# CONNECTOR.net
KiCad netlist of a schematic drawn in Altium Designer
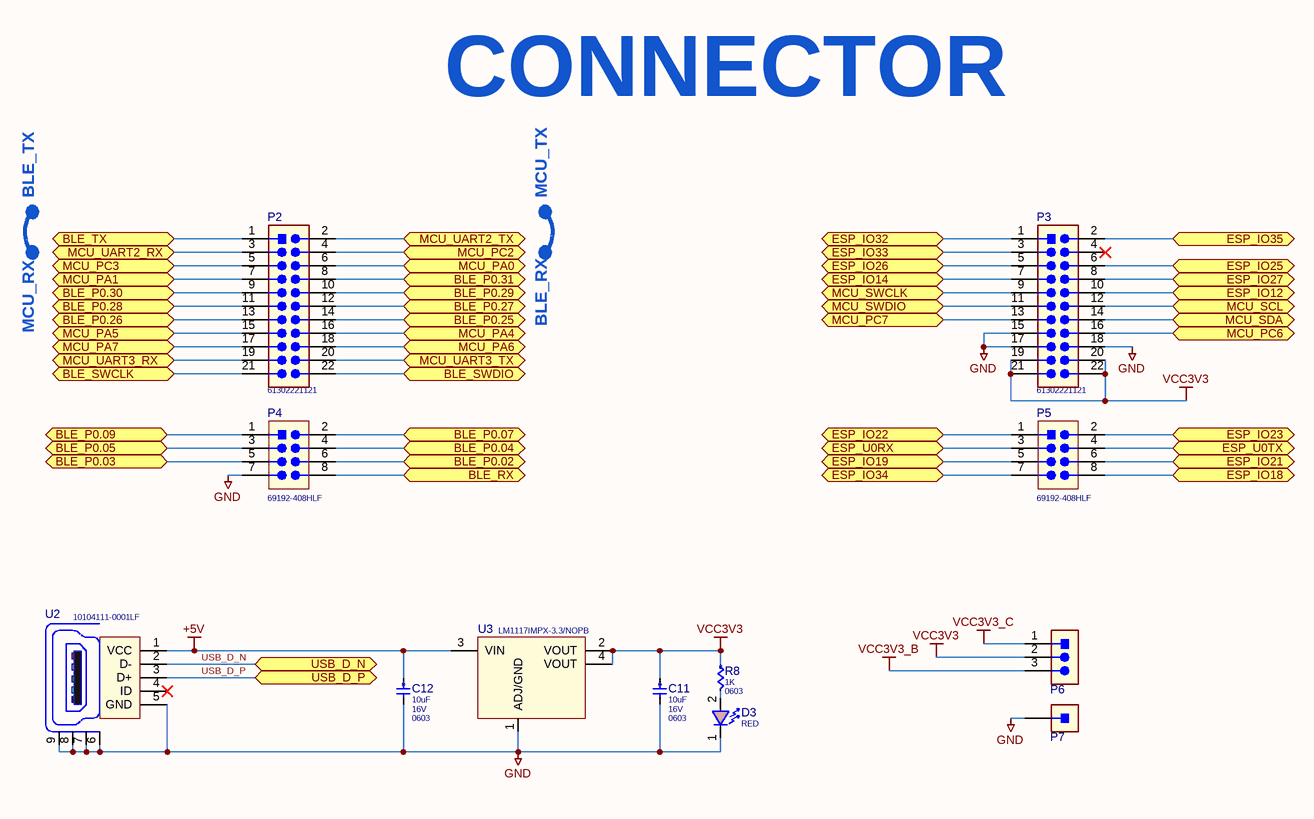
[diagram p0: CONNECTOR.SchDoc]

(export (version "E")
  (design (tool "Eeschema 10.0.6"))
  (components
    (comp (ref "C11")
      (value "10uF")
      (footprint "C0603")
      (description "CAP CER 10UF 10% 16V X5R 0603 SMD")
      (fields
        (field (name "TOLERANCE") "10%")
        (field (name "VOLTAGE") "16V")
        (field (name "PACK") "0603")
        (field (name "Comment") "10uF 16V 0603")
      )
      (libsource (lib "FENIKAA_LIB") (part "C0603_10uF_16V_10%"))
    )
    (comp (ref "C12")
      (value "10uF")
      (footprint "C0603")
      (description "CAP CER 10UF 10% 16V X5R 0603 SMD")
      (fields
        (field (name "TOLERANCE") "10%")
        (field (name "VOLTAGE") "16V")
        (field (name "PACK") "0603")
        (field (name "Comment") "10uF 16V 0603")
      )
      (libsource (lib "FENIKAA_LIB") (part "C0603_10uF_16V_10%"))
    )
    (comp (ref "D3")
      (value "LH R974-LP-1")
      (footprint "LED0805_RED")
      (description "LED IND RED 1.8V 20mA 0805 SMD")
      (fields (field (name "COLOR") "RED"))
      (libsource (lib "FENIKAA_LIB") (part "LED0805_RED"))
    )
    (comp (ref "P2")
      (value "61302221121")
      (footprint "CON_22_2.54")
      (description "CON C2B 2R11C M 2.54P THR")
      (fields (field (name "MGR PN") "61302221121"))
      (libsource (lib "FENIKAA_LIB") (part "CON_2x11"))
    )
    (comp (ref "P3")
      (value "61302221121")
      (footprint "CON_22_2.54")
      (description "CON C2B 2R11C M 2.54P THR")
      (fields (field (name "MGR PN") "61302221121"))
      (libsource (lib "FENIKAA_LIB") (part "CON_2x11"))
    )
    (comp (ref "P4")
      (value "69192-408HLF")
      (footprint "CON_2x4_2.54P")
      (description "CON C2B 2R4C M 2.54P THR")
      (fields (field (name "MGR PN") "69192-408HLF"))
      (libsource (lib "FENIKAA_LIB") (part "CON_2x4"))
    )
    (comp (ref "P5")
      (value "69192-408HLF")
      (footprint "CON_2x4_2.54P")
      (description "CON C2B 2R4C M 2.54P THR")
      (fields (field (name "MGR PN") "69192-408HLF"))
      (libsource (lib "FENIKAA_LIB") (part "CON_2x4"))
    )
    (comp (ref "P6")
      (value "CON3")
      (footprint "CON_3_2.54")
      (description "CONNECTOR 3POS 2.54")
      (libsource (lib "FENIKAA_LIB") (part "CON3"))
    )
    (comp (ref "P7")
      (value "PAD_2.54")
      (footprint "CONN_1")
      (libsource (lib "FENIKAA_LIB") (part "PAD_2.54"))
    )
    (comp (ref "R8")
      (value "1K")
      (footprint "R0603")
      (description "RES CHP 1K 1% 1/10W 0603 SMD")
      (fields (field (name "POWER") "1/10W") (field (name "PACK") "0603") (field (name "TOLERANCE") "1%"))
      (libsource (lib "FENIKAA_LIB") (part "R0603_1K_1/10W_1%"))
    )
    (comp (ref "U2")
      (value "10104111-0001LF")
      (footprint "USB-MICRO-AB")
      (description "CON USB 2.0 MICRO AB SMD")
      (fields (field (name "MGR PN") "10104111-0001LF"))
      (libsource (lib "FENIKAA_LIB") (part "CON_USB_MICRO"))
    )
    (comp (ref "U3")
      (value "LM1117IMPX-3.3/NOPB")
      (footprint "SOT-223-4")
      (description "ICS PMI VREG 3.3V 800mA SOT-223-4 SMD")
      (fields (field (name "MGR PN") "LM1117IMPX-3.3/NOPB"))
      (libsource (lib "FENIKAA_LIB") (part "IC_LM1117IMPX-3.3/NOPB"))
    )
  )
  (nets
    (net (code "1") (name "+5V") (class "Default")
      (node (ref "C12") (pin "1") (pinfunction "1_1") (pintype "passive"))
      (node (ref "U2") (pin "1") (pinfunction "VCC_1") (pintype "passive"))
      (node (ref "U3") (pin "3") (pinfunction "VIN_3") (pintype "passive"))
    )
    (net (code "2") (name "/BLE_P0.02") (class "Default")
      (node (ref "P4") (pin "6") (pinfunction "6_6") (pintype "passive"))
    )
    (net (code "3") (name "/BLE_P0.03") (class "Default")
      (node (ref "P4") (pin "5") (pinfunction "5_5") (pintype "passive"))
    )
    (net (code "4") (name "/BLE_P0.04") (class "Default")
      (node (ref "P4") (pin "4") (pinfunction "4_4") (pintype "passive"))
    )
    (net (code "5") (name "/BLE_P0.05") (class "Default")
      (node (ref "P4") (pin "3") (pinfunction "3_3") (pintype "passive"))
    )
    (net (code "6") (name "/BLE_P0.07") (class "Default")
      (node (ref "P4") (pin "2") (pinfunction "2_2") (pintype "passive"))
    )
    (net (code "7") (name "/BLE_P0.09") (class "Default")
      (node (ref "P4") (pin "1") (pinfunction "1_1") (pintype "passive"))
    )
    (net (code "8") (name "/BLE_P0.25") (class "Default")
      (node (ref "P2") (pin "14") (pinfunction "14_14") (pintype "passive"))
    )
    (net (code "9") (name "/BLE_P0.26") (class "Default")
      (node (ref "P2") (pin "13") (pinfunction "13_13") (pintype "passive"))
    )
    (net (code "10") (name "/BLE_P0.27") (class "Default")
      (node (ref "P2") (pin "12") (pinfunction "12_12") (pintype "passive"))
    )
    (net (code "11") (name "/BLE_P0.28") (class "Default")
      (node (ref "P2") (pin "11") (pinfunction "11_11") (pintype "passive"))
    )
    (net (code "12") (name "/BLE_P0.29") (class "Default")
      (node (ref "P2") (pin "10") (pinfunction "10_10") (pintype "passive"))
    )
    (net (code "13") (name "/BLE_P0.30") (class "Default")
      (node (ref "P2") (pin "9") (pinfunction "9_9") (pintype "passive"))
    )
    (net (code "14") (name "/BLE_P0.31") (class "Default")
      (node (ref "P2") (pin "8") (pinfunction "8_8") (pintype "passive"))
    )
    (net (code "15") (name "/BLE_RX") (class "Default")
      (node (ref "P4") (pin "8") (pinfunction "8_8") (pintype "passive"))
    )
    (net (code "16") (name "/BLE_SWCLK") (class "Default")
      (node (ref "P2") (pin "21") (pinfunction "21_21") (pintype "passive"))
    )
    (net (code "17") (name "/BLE_SWDIO") (class "Default")
      (node (ref "P2") (pin "22") (pinfunction "22_22") (pintype "passive"))
    )
    (net (code "18") (name "/BLE_TX") (class "Default")
      (node (ref "P2") (pin "1") (pinfunction "1_1") (pintype "passive"))
    )
    (net (code "19") (name "/ESP_IO12") (class "Default")
      (node (ref "P3") (pin "10") (pinfunction "10_10") (pintype "passive"))
    )
    (net (code "20") (name "/ESP_IO14") (class "Default")
      (node (ref "P3") (pin "7") (pinfunction "7_7") (pintype "passive"))
    )
    (net (code "21") (name "/ESP_IO18") (class "Default")
      (node (ref "P5") (pin "8") (pinfunction "8_8") (pintype "passive"))
    )
    (net (code "22") (name "/ESP_IO19") (class "Default")
      (node (ref "P5") (pin "5") (pinfunction "5_5") (pintype "passive"))
    )
    (net (code "23") (name "/ESP_IO21") (class "Default")
      (node (ref "P5") (pin "6") (pinfunction "6_6") (pintype "passive"))
    )
    (net (code "24") (name "/ESP_IO22") (class "Default")
      (node (ref "P5") (pin "1") (pinfunction "1_1") (pintype "passive"))
    )
    (net (code "25") (name "/ESP_IO23") (class "Default")
      (node (ref "P5") (pin "2") (pinfunction "2_2") (pintype "passive"))
    )
    (net (code "26") (name "/ESP_IO25") (class "Default")
      (node (ref "P3") (pin "6") (pinfunction "6_6") (pintype "passive"))
    )
    (net (code "27") (name "/ESP_IO26") (class "Default")
      (node (ref "P3") (pin "5") (pinfunction "5_5") (pintype "passive"))
    )
    (net (code "28") (name "/ESP_IO27") (class "Default")
      (node (ref "P3") (pin "8") (pinfunction "8_8") (pintype "passive"))
    )
    (net (code "29") (name "/ESP_IO32") (class "Default")
      (node (ref "P3") (pin "1") (pinfunction "1_1") (pintype "passive"))
    )
    (net (code "30") (name "/ESP_IO33") (class "Default")
      (node (ref "P3") (pin "3") (pinfunction "3_3") (pintype "passive"))
    )
    (net (code "31") (name "/ESP_IO34") (class "Default")
      (node (ref "P5") (pin "7") (pinfunction "7_7") (pintype "passive"))
    )
    (net (code "32") (name "/ESP_IO35") (class "Default")
      (node (ref "P3") (pin "2") (pinfunction "2_2") (pintype "passive"))
    )
    (net (code "33") (name "/ESP_U0RX") (class "Default")
      (node (ref "P5") (pin "3") (pinfunction "3_3") (pintype "passive"))
    )
    (net (code "34") (name "/ESP_U0TX") (class "Default")
      (node (ref "P5") (pin "4") (pinfunction "4_4") (pintype "passive"))
    )
    (net (code "35") (name "/MCU_PA0") (class "Default")
      (node (ref "P2") (pin "6") (pinfunction "6_6") (pintype "passive"))
    )
    (net (code "36") (name "/MCU_PA1") (class "Default")
      (node (ref "P2") (pin "7") (pinfunction "7_7") (pintype "passive"))
    )
    (net (code "37") (name "/MCU_PA4") (class "Default")
      (node (ref "P2") (pin "16") (pinfunction "16_16") (pintype "passive"))
    )
    (net (code "38") (name "/MCU_PA5") (class "Default")
      (node (ref "P2") (pin "15") (pinfunction "15_15") (pintype "passive"))
    )
    (net (code "39") (name "/MCU_PA6") (class "Default")
      (node (ref "P2") (pin "18") (pinfunction "18_18") (pintype "passive"))
    )
    (net (code "40") (name "/MCU_PA7") (class "Default")
      (node (ref "P2") (pin "17") (pinfunction "17_17") (pintype "passive"))
    )
    (net (code "41") (name "/MCU_PC2") (class "Default")
      (node (ref "P2") (pin "4") (pinfunction "4_4") (pintype "passive"))
    )
    (net (code "42") (name "/MCU_PC3") (class "Default")
      (node (ref "P2") (pin "5") (pinfunction "5_5") (pintype "passive"))
    )
    (net (code "43") (name "/MCU_PC6") (class "Default")
      (node (ref "P3") (pin "16") (pinfunction "16_16") (pintype "passive"))
    )
    (net (code "44") (name "/MCU_PC7") (class "Default")
      (node (ref "P3") (pin "13") (pinfunction "13_13") (pintype "passive"))
    )
    (net (code "45") (name "/MCU_SCL") (class "Default")
      (node (ref "P3") (pin "12") (pinfunction "12_12") (pintype "passive"))
    )
    (net (code "46") (name "/MCU_SDA") (class "Default")
      (node (ref "P3") (pin "14") (pinfunction "14_14") (pintype "passive"))
    )
    (net (code "47") (name "/MCU_SWCLK") (class "Default")
      (node (ref "P3") (pin "9") (pinfunction "9_9") (pintype "passive"))
    )
    (net (code "48") (name "/MCU_SWDIO") (class "Default")
      (node (ref "P3") (pin "11") (pinfunction "11_11") (pintype "passive"))
    )
    (net (code "49") (name "/MCU_UART2_RX") (class "Default")
      (node (ref "P2") (pin "3") (pinfunction "3_3") (pintype "passive"))
    )
    (net (code "50") (name "/MCU_UART2_TX") (class "Default")
      (node (ref "P2") (pin "2") (pinfunction "2_2") (pintype "passive"))
    )
    (net (code "51") (name "/MCU_UART3_RX") (class "Default")
      (node (ref "P2") (pin "19") (pinfunction "19_19") (pintype "passive"))
    )
    (net (code "52") (name "/MCU_UART3_TX") (class "Default")
      (node (ref "P2") (pin "20") (pinfunction "20_20") (pintype "passive"))
    )
    (net (code "53") (name "/USB_D_N") (class "Default")
      (node (ref "U2") (pin "2") (pinfunction "D-_2") (pintype "passive"))
    )
    (net (code "54") (name "/USB_D_P") (class "Default")
      (node (ref "U2") (pin "3") (pinfunction "D+_3") (pintype "passive"))
    )
    (net (code "55") (name "GND") (class "Default")
      (node (ref "C11") (pin "2") (pinfunction "2_2") (pintype "passive"))
      (node (ref "C12") (pin "2") (pinfunction "2_2") (pintype "passive"))
      (node (ref "D3") (pin "1") (pinfunction "K_1") (pintype "passive"))
      (node (ref "P3") (pin "15") (pinfunction "15_15") (pintype "passive"))
      (node (ref "P3") (pin "17") (pinfunction "17_17") (pintype "passive"))
      (node (ref "P3") (pin "18") (pinfunction "18_18") (pintype "passive"))
      (node (ref "P4") (pin "7") (pinfunction "7_7") (pintype "passive"))
      (node (ref "P7") (pin "1") (pinfunction "1_1") (pintype "passive"))
      (node (ref "U2") (pin "5") (pinfunction "GND_5") (pintype "passive"))
      (node (ref "U2") (pin "6") (pinfunction "Shield_6") (pintype "passive"))
      (node (ref "U2") (pin "7") (pinfunction "Shield_7") (pintype "passive"))
      (node (ref "U2") (pin "8") (pinfunction "Shield_8") (pintype "passive"))
      (node (ref "U2") (pin "9") (pinfunction "Shield_9") (pintype "passive"))
      (node (ref "U3") (pin "1") (pinfunction "ADJ/GND_1") (pintype "passive"))
    )
    (net (code "56") (name "Net-(D3-A)") (class "Default")
      (node (ref "D3") (pin "2") (pinfunction "A_2") (pintype "passive"))
      (node (ref "R8") (pin "2") (pinfunction "2_2") (pintype "passive"))
    )
    (net (code "57") (name "VCC3V3") (class "Default")
      (node (ref "C11") (pin "1") (pinfunction "1_1") (pintype "passive"))
      (node (ref "P3") (pin "19") (pinfunction "19_19") (pintype "passive"))
      (node (ref "P3") (pin "20") (pinfunction "20_20") (pintype "passive"))
      (node (ref "P3") (pin "21") (pinfunction "21_21") (pintype "passive"))
      (node (ref "P3") (pin "22") (pinfunction "22_22") (pintype "passive"))
      (node (ref "P6") (pin "2") (pinfunction "2_2") (pintype "passive"))
      (node (ref "R8") (pin "1") (pinfunction "1_1") (pintype "passive"))
      (node (ref "U3") (pin "2") (pinfunction "VOUT_2") (pintype "passive"))
      (node (ref "U3") (pin "4") (pinfunction "VOUT_4") (pintype "passive"))
    )
    (net (code "58") (name "VCC3V3_B") (class "Default")
      (node (ref "P6") (pin "3") (pinfunction "3_3") (pintype "passive"))
    )
    (net (code "59") (name "VCC3V3_C") (class "Default")
      (node (ref "P6") (pin "1") (pinfunction "1_1") (pintype "passive"))
    )
    (net (code "60") (name "unconnected-(P3-Pad4)") (class "Default")
      (node (ref "P3") (pin "4") (pinfunction "4_4") (pintype "passive+no_connect"))
    )
    (net (code "61") (name "unconnected-(U2-ID-Pad4)") (class "Default")
      (node (ref "U2") (pin "4") (pinfunction "ID_4") (pintype "passive+no_connect"))
    )
  )
)
